# MAX96717_PINOUT.net
KiCad netlist of a schematic drawn in Altium Designer
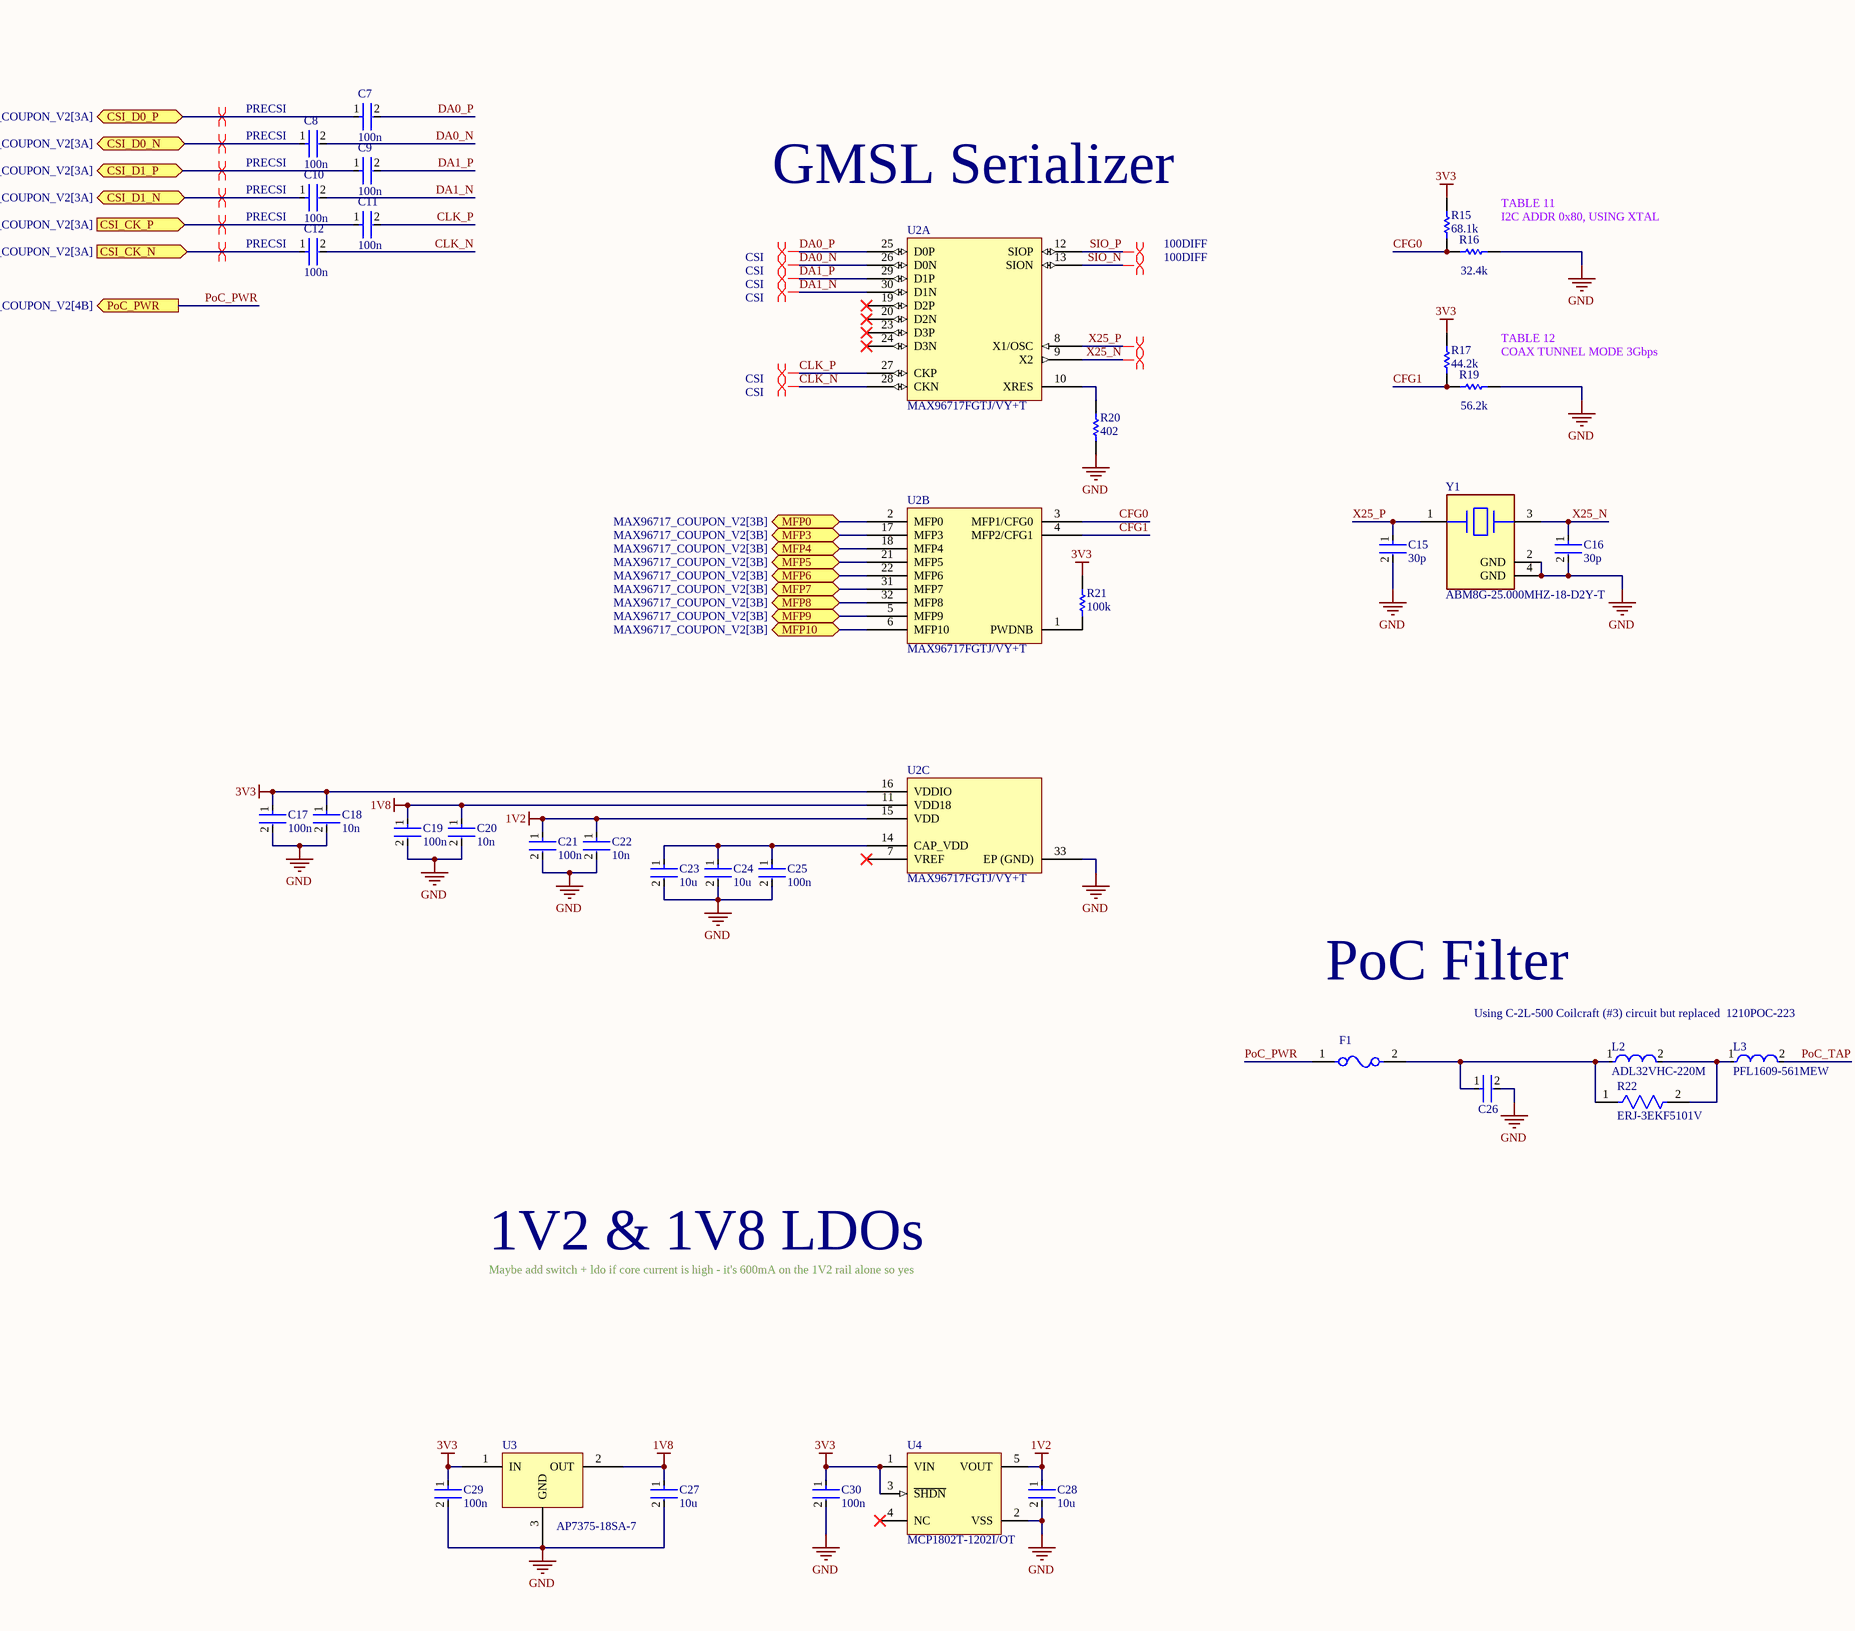
[diagram p0: MAX96717_PINOUT.SchDoc, left]
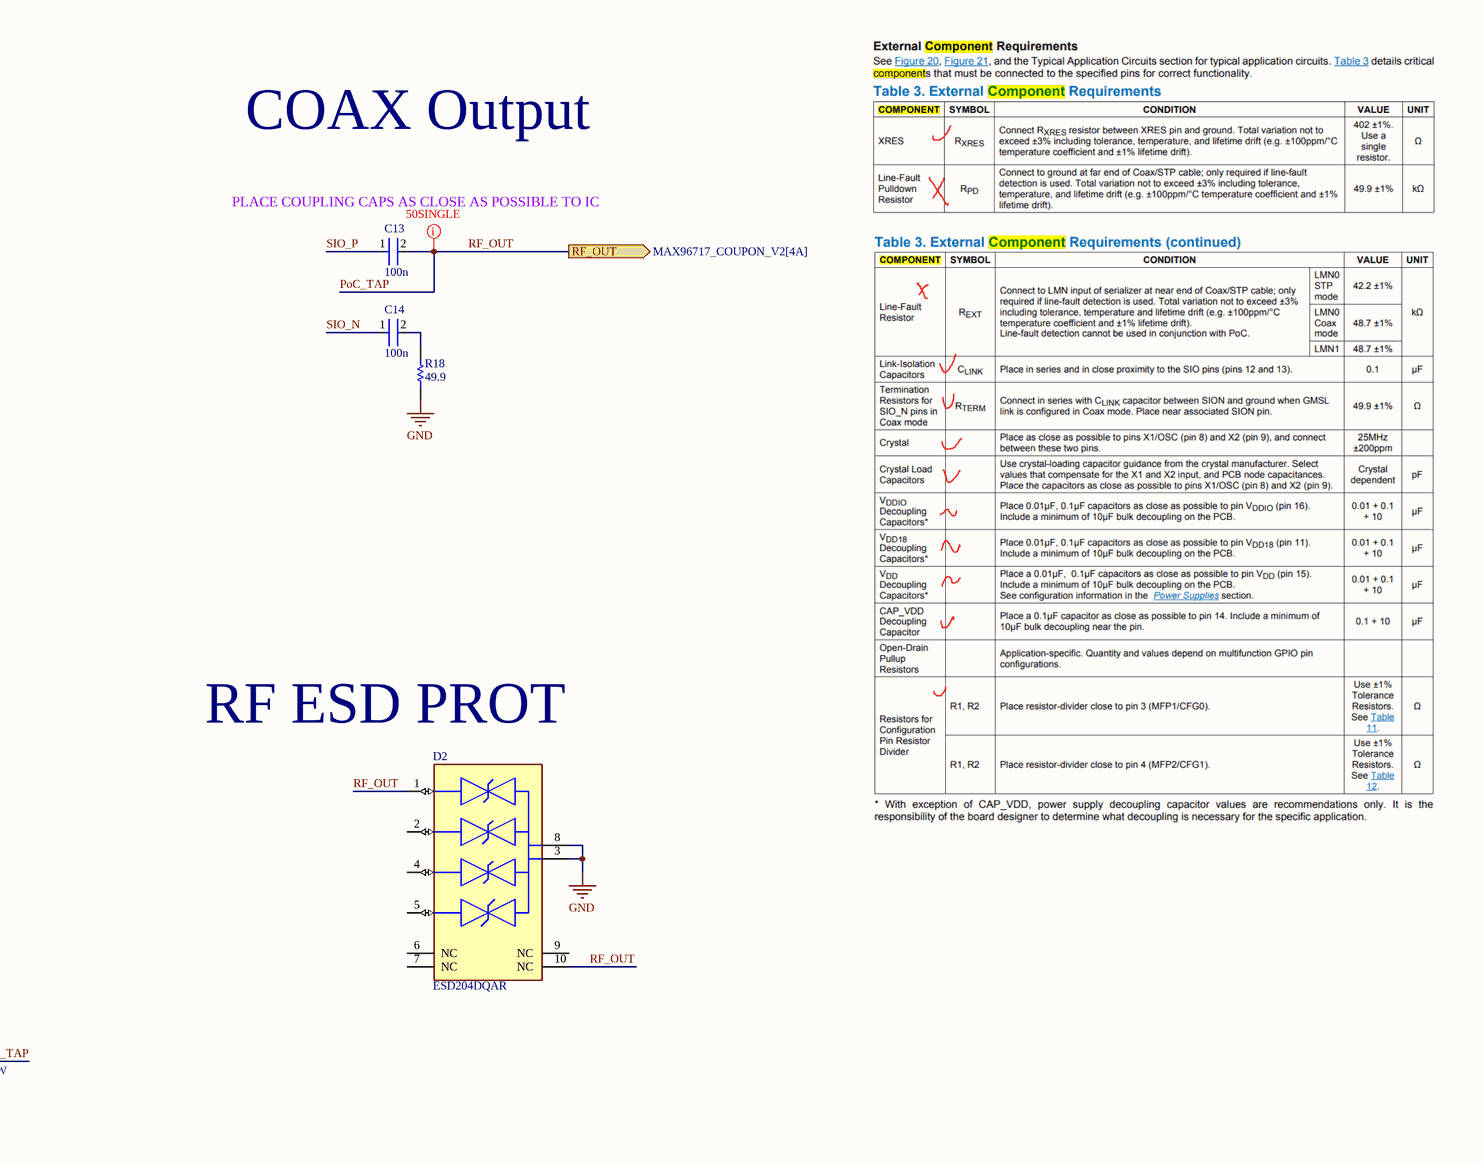
[diagram p1: MAX96717_PINOUT.SchDoc, right]

(export (version "E")
  (design (tool "Eeschema 10.0.6"))
  (components
    (comp (ref "C7")
      (value "100n")
      (footprint "FP-0402-L_1_0_0_05-W_0_5-IPC_A")
      (description "LARGE PADS, 0402 CAP, CHANGE COMMENT TO MATCH REAL P/N")
      (libsource (lib "Space Concordia") (part "b4654b650e69147ec39a6b967a45e02"))
    )
    (comp (ref "C8")
      (value "100n")
      (footprint "FP-0402-L_1_0_0_05-W_0_5-IPC_A")
      (description "LARGE PADS, 0402 CAP, CHANGE COMMENT TO MATCH REAL P/N")
      (libsource (lib "Space Concordia") (part "b4654b650e69147ec39a6b967a45e02"))
    )
    (comp (ref "C9")
      (value "100n")
      (footprint "FP-0402-L_1_0_0_05-W_0_5-IPC_A")
      (description "LARGE PADS, 0402 CAP, CHANGE COMMENT TO MATCH REAL P/N")
      (libsource (lib "Space Concordia") (part "b4654b650e69147ec39a6b967a45e02"))
    )
    (comp (ref "C10")
      (value "100n")
      (footprint "FP-0402-L_1_0_0_05-W_0_5-IPC_A")
      (description "LARGE PADS, 0402 CAP, CHANGE COMMENT TO MATCH REAL P/N")
      (libsource (lib "Space Concordia") (part "b4654b650e69147ec39a6b967a45e02"))
    )
    (comp (ref "C11")
      (value "100n")
      (footprint "FP-0402-L_1_0_0_05-W_0_5-IPC_A")
      (description "LARGE PADS, 0402 CAP, CHANGE COMMENT TO MATCH REAL P/N")
      (libsource (lib "Space Concordia") (part "b4654b650e69147ec39a6b967a45e02"))
    )
    (comp (ref "C12")
      (value "100n")
      (footprint "FP-0402-L_1_0_0_05-W_0_5-IPC_A")
      (description "LARGE PADS, 0402 CAP, CHANGE COMMENT TO MATCH REAL P/N")
      (libsource (lib "Space Concordia") (part "b4654b650e69147ec39a6b967a45e02"))
    )
    (comp (ref "C13")
      (value "100n")
      (footprint "FP-0402-L_1_0_0_05-W_0_5-IPC_A")
      (description "LARGE PADS, 0402 CAP, CHANGE COMMENT TO MATCH REAL P/N")
      (libsource (lib "Space Concordia") (part "b4654b650e69147ec39a6b967a45e02"))
    )
    (comp (ref "C14")
      (value "100n")
      (footprint "FP-0402-L_1_0_0_05-W_0_5-IPC_A")
      (description "LARGE PADS, 0402 CAP, CHANGE COMMENT TO MATCH REAL P/N")
      (libsource (lib "Space Concordia") (part "b4654b650e69147ec39a6b967a45e02"))
    )
    (comp (ref "C15")
      (value "30p")
      (footprint "FP-0402-L_1_0_0_05-W_0_5-IPC_A")
      (description "LARGE PADS, 0402 CAP, CHANGE COMMENT TO MATCH REAL P/N")
      (libsource (lib "Space Concordia") (part "b4654b650e69147ec39a6b967a45e02"))
    )
    (comp (ref "C16")
      (value "30p")
      (footprint "FP-0402-L_1_0_0_05-W_0_5-IPC_A")
      (description "LARGE PADS, 0402 CAP, CHANGE COMMENT TO MATCH REAL P/N")
      (libsource (lib "Space Concordia") (part "b4654b650e69147ec39a6b967a45e02"))
    )
    (comp (ref "C17")
      (value "100n")
      (footprint "FP-0402-L_1_0_0_05-W_0_5-IPC_A")
      (description "LARGE PADS, 0402 CAP, CHANGE COMMENT TO MATCH REAL P/N")
      (libsource (lib "Space Concordia") (part "b4654b650e69147ec39a6b967a45e02"))
    )
    (comp (ref "C18")
      (value "10n")
      (footprint "FP-0402-L_1_0_0_05-W_0_5-IPC_A")
      (description "LARGE PADS, 0402 CAP, CHANGE COMMENT TO MATCH REAL P/N")
      (libsource (lib "Space Concordia") (part "b4654b650e69147ec39a6b967a45e02"))
    )
    (comp (ref "C19")
      (value "100n")
      (footprint "FP-0402-L_1_0_0_05-W_0_5-IPC_A")
      (description "LARGE PADS, 0402 CAP, CHANGE COMMENT TO MATCH REAL P/N")
      (libsource (lib "Space Concordia") (part "b4654b650e69147ec39a6b967a45e02"))
    )
    (comp (ref "C20")
      (value "10n")
      (footprint "FP-0402-L_1_0_0_05-W_0_5-IPC_A")
      (description "LARGE PADS, 0402 CAP, CHANGE COMMENT TO MATCH REAL P/N")
      (libsource (lib "Space Concordia") (part "b4654b650e69147ec39a6b967a45e02"))
    )
    (comp (ref "C21")
      (value "100n")
      (footprint "FP-0402-L_1_0_0_05-W_0_5-IPC_A")
      (description "LARGE PADS, 0402 CAP, CHANGE COMMENT TO MATCH REAL P/N")
      (libsource (lib "Space Concordia") (part "b4654b650e69147ec39a6b967a45e02"))
    )
    (comp (ref "C22")
      (value "10n")
      (footprint "FP-0402-L_1_0_0_05-W_0_5-IPC_A")
      (description "LARGE PADS, 0402 CAP, CHANGE COMMENT TO MATCH REAL P/N")
      (libsource (lib "Space Concordia") (part "b4654b650e69147ec39a6b967a45e02"))
    )
    (comp (ref "C23")
      (value "10u")
      (footprint "FP-0402-L_1_0_0_05-W_0_5-IPC_A")
      (description "LARGE PADS, 0402 CAP, CHANGE COMMENT TO MATCH REAL P/N")
      (libsource (lib "Space Concordia") (part "b4654b650e69147ec39a6b967a45e02"))
    )
    (comp (ref "C24")
      (value "10u")
      (footprint "FP-0402-L_1_0_0_05-W_0_5-IPC_A")
      (description "LARGE PADS, 0402 CAP, CHANGE COMMENT TO MATCH REAL P/N")
      (libsource (lib "Space Concordia") (part "b4654b650e69147ec39a6b967a45e02"))
    )
    (comp (ref "C25")
      (value "100n")
      (footprint "FP-0402-L_1_0_0_05-W_0_5-IPC_A")
      (description "LARGE PADS, 0402 CAP, CHANGE COMMENT TO MATCH REAL P/N")
      (libsource (lib "Space Concordia") (part "b4654b650e69147ec39a6b967a45e02"))
    )
    (comp (ref "C26")
      (value "GRM21BR61E226ME44L")
      (footprint "FP-GRM21B-0_2-e0_2_0_7-IPC_B")
      (description "Chip Multilayer Ceramic Capacitors for General Purpose, 0805, 22uF, X5R, 15%, 20%, 25V")
      (fields (field (name "TOLERANCE") "20%") (field (name "VOLTAGE") "25V"))
      (libsource (lib "Altium Content Vault") (part "b4654b650e69147ec39a6b967a45e02"))
    )
    (comp (ref "C27")
      (value "10u")
      (footprint "FP-0402-L_1_0_0_05-W_0_5-IPC_A")
      (description "LARGE PADS, 0402 CAP, CHANGE COMMENT TO MATCH REAL P/N")
      (libsource (lib "Space Concordia") (part "b4654b650e69147ec39a6b967a45e02"))
    )
    (comp (ref "C28")
      (value "10u")
      (footprint "FP-0402-L_1_0_0_05-W_0_5-IPC_A")
      (description "LARGE PADS, 0402 CAP, CHANGE COMMENT TO MATCH REAL P/N")
      (libsource (lib "Space Concordia") (part "b4654b650e69147ec39a6b967a45e02"))
    )
    (comp (ref "C29")
      (value "100n")
      (footprint "FP-0402-L_1_0_0_05-W_0_5-IPC_A")
      (description "LARGE PADS, 0402 CAP, CHANGE COMMENT TO MATCH REAL P/N")
      (libsource (lib "Space Concordia") (part "b4654b650e69147ec39a6b967a45e02"))
    )
    (comp (ref "C30")
      (value "100n")
      (footprint "FP-0402-L_1_0_0_05-W_0_5-IPC_A")
      (description "LARGE PADS, 0402 CAP, CHANGE COMMENT TO MATCH REAL P/N")
      (libsource (lib "Space Concordia") (part "b4654b650e69147ec39a6b967a45e02"))
    )
    (comp (ref "D2")
      (value "ESD204DQAR")
      (footprint "FP-DQA0010A-MFG")
      (description "4-CHANNEL LOW-CAPACITANCE SURGE")
      (fields
        (field (name "MANUFACTURER") "Texas Instruments")
        (field (name "OCTOPART") "https://octopart.com/esd204dqar-texas+instruments-89917476")
      )
      (libsource (lib "Altium Content Vault") (part "1465e58c1818c7767b55926832f0bf5"))
    )
    (comp (ref "F1")
      (value "MF-FSMF050X-2")
      (footprint "FP-MF-FSMF-MFG")
      (description "PTC RESET FUSE 6V 500MA 0603")
      (fields
        (field (name "MANUFACTURER") "Bourns Inc.")
        (field (name "OCTOPART") "https://octopart.com/mf-fsmf050x-2-bourns-10470804")
      )
      (libsource (lib "Altium Content Vault") (part "5bcf9b9f640e542cf0359d10258e979"))
    )
    (comp (ref "L2")
      (value "ADL32VHC-220M")
      (footprint "FP-1210POC-MFG")
      (description "NOT COILCRAFT - ACTUAL P# --> ADL32VHC-220M\r\n - Power Injection Chokes for PoC")
      (fields
        (field (name "MANUFACTURER") "coilcraft")
        (field (name "OCTOPART") "https://octopart.com/1210poc-223mrc-coilcraft-103207315")
      )
      (libsource (lib "Altium Content Vault") (part "725321dda6339637d4d059423bc1c3c"))
    )
    (comp (ref "L3")
      (value "PFL1609-561MEW")
      (footprint "FP-PFL1609-MFG")
      (description "Fixed Inductors PFL1609 Low Profile 0.56 uH 20 % 1.4 A")
      (fields (field (name "MANUFACTURER") "coilcraft") (field (name "TOLERANCE") "20%"))
      (libsource (lib "Altium Content Vault") (part "725321dda6339637d4d059423bc1c3c"))
    )
    (comp (ref "R15")
      (value "68.1k")
      (footprint "R0603B")
      (description "Resistor")
      (libsource (lib "Space Concordia") (part "Resistor"))
    )
    (comp (ref "R16")
      (value "32.4k")
      (footprint "R0603B")
      (description "Resistor")
      (libsource (lib "Space Concordia") (part "Resistor"))
    )
    (comp (ref "R17")
      (value "44.2k")
      (footprint "R0603B")
      (description "Resistor")
      (libsource (lib "Space Concordia") (part "Resistor"))
    )
    (comp (ref "R18")
      (value "49.9")
      (footprint "R0603B")
      (description "Resistor")
      (libsource (lib "Space Concordia") (part "Resistor"))
    )
    (comp (ref "R19")
      (value "56.2k")
      (footprint "R0603B")
      (description "Resistor")
      (libsource (lib "Space Concordia") (part "Resistor"))
    )
    (comp (ref "R20")
      (value "402")
      (footprint "R0603B")
      (description "Resistor")
      (libsource (lib "Space Concordia") (part "Resistor"))
    )
    (comp (ref "R21")
      (value "100k")
      (footprint "R0603B")
      (description "Resistor")
      (libsource (lib "Space Concordia") (part "Resistor"))
    )
    (comp (ref "R22")
      (value "ERJ-3EKF5101V")
      (footprint "FP-ERJ3EK-MFG")
      (description "RES SMD 5.1K OHM 1% 1/10W 0603")
      (fields (field (name "TOLERANCE") "1%"))
      (libsource (lib "Altium Content Vault") (part "1029c3af85768c4190bb7ad29bc67b5"))
    )
    (comp (ref "U2")
      (value "MAX96717FGTJ/VY+T")
      (footprint "QFN50P500X500X80_HS-33N")
      (description "3Gbps Serializer TQFN-32 Serializers / Deserializers ROHS")
      (libsource (lib "Space Concordia") (part "MAX96717FGTJ_VY+T"))
    )
    (comp (ref "U3")
      (value "AP7375-18SA-7")
      (footprint "AP7375-18SA-7-Footprint-1")
      (description "Fixed Positive LDO Regulator")
      (libsource (lib "Space Concordia") (part "AP7375-18SA-7"))
    )
    (comp (ref "U4")
      (value "MCP1802T-1202I/OT")
      (footprint "SOT-23-OT5_M")
      (description "300 mA, High PSRR, Low Quiescent Current LDO, 5-Pin SOT-23, Industrial Temperature, Tape and Reel")
      (libsource (lib "Altium Content Vault") (part "PM-LINEREG-MCP1802-IL5"))
    )
    (comp (ref "Y1")
      (value "ABM8G-25.000MHZ-18-D2Y-T")
      (footprint "FP-ABM8G-MFG")
      (description "Crystal 25MHz ±20ppm (Tol) ±30ppm (Stability) 18pF FUND 60Ω 4-Pin SMD T/R")
      (fields (field (name "TOLERANCE") "20ppm"))
      (libsource (lib "Altium Content Vault") (part "48e526d86b7f2615d98721063c72f49"))
    )
  )
  (nets
    (net (code "1") (name "/CFG0") (class "Default")
      (node (ref "R15") (pin "1") (pinfunction "1_1") (pintype "passive"))
      (node (ref "R16") (pin "2") (pinfunction "2_2") (pintype "passive"))
      (node (ref "U2") (pin "3") (pinfunction "MFP1/CFG0_3") (pintype "passive"))
    )
    (net (code "2") (name "/CFG1") (class "Default")
      (node (ref "R17") (pin "1") (pinfunction "1_1") (pintype "passive"))
      (node (ref "R19") (pin "2") (pinfunction "2_2") (pintype "passive"))
      (node (ref "U2") (pin "4") (pinfunction "MFP2/CFG1_4") (pintype "passive"))
    )
    (net (code "3") (name "/CLK_N") (class "Default")
      (node (ref "C12") (pin "2") (pinfunction "2_2") (pintype "passive"))
      (node (ref "U2") (pin "28") (pinfunction "CKN_28") (pintype "bidirectional"))
    )
    (net (code "4") (name "/CLK_P") (class "Default")
      (node (ref "C11") (pin "2") (pinfunction "2_2") (pintype "passive"))
      (node (ref "U2") (pin "27") (pinfunction "CKP_27") (pintype "bidirectional"))
    )
    (net (code "5") (name "/CSI_CK_N") (class "Default")
      (node (ref "C12") (pin "1") (pinfunction "1_1") (pintype "passive"))
    )
    (net (code "6") (name "/CSI_CK_P") (class "Default")
      (node (ref "C11") (pin "1") (pinfunction "1_1") (pintype "passive"))
    )
    (net (code "7") (name "/CSI_D0_N") (class "Default")
      (node (ref "C8") (pin "1") (pinfunction "1_1") (pintype "passive"))
    )
    (net (code "8") (name "/CSI_D0_P") (class "Default")
      (node (ref "C7") (pin "1") (pinfunction "1_1") (pintype "passive"))
    )
    (net (code "9") (name "/CSI_D1_N") (class "Default")
      (node (ref "C10") (pin "1") (pinfunction "1_1") (pintype "passive"))
    )
    (net (code "10") (name "/CSI_D1_P") (class "Default")
      (node (ref "C9") (pin "1") (pinfunction "1_1") (pintype "passive"))
    )
    (net (code "11") (name "/DA0_N") (class "Default")
      (node (ref "C8") (pin "2") (pinfunction "2_2") (pintype "passive"))
      (node (ref "U2") (pin "26") (pinfunction "D0N_26") (pintype "bidirectional"))
    )
    (net (code "12") (name "/DA0_P") (class "Default")
      (node (ref "C7") (pin "2") (pinfunction "2_2") (pintype "passive"))
      (node (ref "U2") (pin "25") (pinfunction "D0P_25") (pintype "bidirectional"))
    )
    (net (code "13") (name "/DA1_N") (class "Default")
      (node (ref "C10") (pin "2") (pinfunction "2_2") (pintype "passive"))
      (node (ref "U2") (pin "30") (pinfunction "D1N_30") (pintype "bidirectional"))
    )
    (net (code "14") (name "/DA1_P") (class "Default")
      (node (ref "C9") (pin "2") (pinfunction "2_2") (pintype "passive"))
      (node (ref "U2") (pin "29") (pinfunction "D1P_29") (pintype "bidirectional"))
    )
    (net (code "15") (name "/MFP0") (class "Default")
      (node (ref "U2") (pin "2") (pinfunction "MFP0_2") (pintype "passive"))
    )
    (net (code "16") (name "/MFP3") (class "Default")
      (node (ref "U2") (pin "17") (pinfunction "MFP3_17") (pintype "passive"))
    )
    (net (code "17") (name "/MFP4") (class "Default")
      (node (ref "U2") (pin "18") (pinfunction "MFP4_18") (pintype "passive"))
    )
    (net (code "18") (name "/MFP5") (class "Default")
      (node (ref "U2") (pin "21") (pinfunction "MFP5_21") (pintype "passive"))
    )
    (net (code "19") (name "/MFP6") (class "Default")
      (node (ref "U2") (pin "22") (pinfunction "MFP6_22") (pintype "passive"))
    )
    (net (code "20") (name "/MFP7") (class "Default")
      (node (ref "U2") (pin "31") (pinfunction "MFP7_31") (pintype "passive"))
    )
    (net (code "21") (name "/MFP8") (class "Default")
      (node (ref "U2") (pin "32") (pinfunction "MFP8_32") (pintype "passive"))
    )
    (net (code "22") (name "/MFP9") (class "Default")
      (node (ref "U2") (pin "5") (pinfunction "MFP9_5") (pintype "passive"))
    )
    (net (code "23") (name "/MFP10") (class "Default")
      (node (ref "U2") (pin "6") (pinfunction "MFP10_6") (pintype "passive"))
    )
    (net (code "24") (name "/PoC_PWR") (class "Default")
      (node (ref "F1") (pin "1") (pinfunction "1_1") (pintype "passive"))
    )
    (net (code "25") (name "/PoC_TAP") (class "Default")
      (node (ref "C13") (pin "2") (pinfunction "2_2") (pintype "passive"))
      (node (ref "D2") (pin "1") (pinfunction "IO1_1") (pintype "bidirectional"))
      (node (ref "D2") (pin "10") (pinfunction "NC_10") (pintype "passive"))
      (node (ref "L3") (pin "2") (pinfunction "2_2") (pintype "passive"))
    )
    (net (code "26") (name "/SIO_N") (class "Default")
      (node (ref "C14") (pin "1") (pinfunction "1_1") (pintype "passive"))
      (node (ref "U2") (pin "13") (pinfunction "SION_13") (pintype "bidirectional"))
    )
    (net (code "27") (name "/SIO_P") (class "Default")
      (node (ref "C13") (pin "1") (pinfunction "1_1") (pintype "passive"))
      (node (ref "U2") (pin "12") (pinfunction "SIOP_12") (pintype "bidirectional"))
    )
    (net (code "28") (name "/X25_N") (class "Default")
      (node (ref "C16") (pin "1") (pinfunction "1_1") (pintype "passive"))
      (node (ref "U2") (pin "9") (pinfunction "X2_9") (pintype "output"))
      (node (ref "Y1") (pin "3") (pinfunction "3_3") (pintype "passive"))
    )
    (net (code "29") (name "/X25_P") (class "Default")
      (node (ref "C15") (pin "1") (pinfunction "1_1") (pintype "passive"))
      (node (ref "U2") (pin "8") (pinfunction "X1/OSC_8") (pintype "input"))
      (node (ref "Y1") (pin "1") (pinfunction "1_1") (pintype "passive"))
    )
    (net (code "30") (name "1V2") (class "Default")
      (node (ref "C21") (pin "1") (pinfunction "1_1") (pintype "passive"))
      (node (ref "C22") (pin "1") (pinfunction "1_1") (pintype "passive"))
      (node (ref "C28") (pin "1") (pinfunction "1_1") (pintype "passive"))
      (node (ref "U2") (pin "15") (pinfunction "VDD_15") (pintype "power_in"))
      (node (ref "U4") (pin "5") (pinfunction "VOUT_5") (pintype "power_in"))
    )
    (net (code "31") (name "1V8") (class "Default")
      (node (ref "C19") (pin "1") (pinfunction "1_1") (pintype "passive"))
      (node (ref "C20") (pin "1") (pinfunction "1_1") (pintype "passive"))
      (node (ref "C27") (pin "1") (pinfunction "1_1") (pintype "passive"))
      (node (ref "U2") (pin "11") (pinfunction "VDD18_11") (pintype "power_in"))
      (node (ref "U3") (pin "2") (pinfunction "OUT_2") (pintype "passive"))
    )
    (net (code "32") (name "3V3") (class "Default")
      (node (ref "C17") (pin "1") (pinfunction "1_1") (pintype "passive"))
      (node (ref "C18") (pin "1") (pinfunction "1_1") (pintype "passive"))
      (node (ref "C29") (pin "1") (pinfunction "1_1") (pintype "passive"))
      (node (ref "C30") (pin "1") (pinfunction "1_1") (pintype "passive"))
      (node (ref "R15") (pin "2") (pinfunction "2_2") (pintype "passive"))
      (node (ref "R17") (pin "2") (pinfunction "2_2") (pintype "passive"))
      (node (ref "R21") (pin "2") (pinfunction "2_2") (pintype "passive"))
      (node (ref "U2") (pin "16") (pinfunction "VDDIO_16") (pintype "power_in"))
      (node (ref "U3") (pin "1") (pinfunction "IN_1") (pintype "passive"))
      (node (ref "U4") (pin "1") (pinfunction "VIN_1") (pintype "power_in"))
      (node (ref "U4") (pin "3") (pinfunction "~{SHDN}_3") (pintype "input"))
    )
    (net (code "33") (name "GND") (class "Default")
      (node (ref "C15") (pin "2") (pinfunction "2_2") (pintype "passive"))
      (node (ref "C16") (pin "2") (pinfunction "2_2") (pintype "passive"))
      (node (ref "C17") (pin "2") (pinfunction "2_2") (pintype "passive"))
      (node (ref "C18") (pin "2") (pinfunction "2_2") (pintype "passive"))
      (node (ref "C19") (pin "2") (pinfunction "2_2") (pintype "passive"))
      (node (ref "C20") (pin "2") (pinfunction "2_2") (pintype "passive"))
      (node (ref "C21") (pin "2") (pinfunction "2_2") (pintype "passive"))
      (node (ref "C22") (pin "2") (pinfunction "2_2") (pintype "passive"))
      (node (ref "C23") (pin "2") (pinfunction "2_2") (pintype "passive"))
      (node (ref "C24") (pin "2") (pinfunction "2_2") (pintype "passive"))
      (node (ref "C25") (pin "2") (pinfunction "2_2") (pintype "passive"))
      (node (ref "C26") (pin "2") (pinfunction "2_2") (pintype "passive"))
      (node (ref "C27") (pin "2") (pinfunction "2_2") (pintype "passive"))
      (node (ref "C28") (pin "2") (pinfunction "2_2") (pintype "passive"))
      (node (ref "C29") (pin "2") (pinfunction "2_2") (pintype "passive"))
      (node (ref "C30") (pin "2") (pinfunction "2_2") (pintype "passive"))
      (node (ref "D2") (pin "3") (pinfunction "GND_3") (pintype "power_in"))
      (node (ref "D2") (pin "8") (pinfunction "GND_8") (pintype "power_in"))
      (node (ref "R16") (pin "1") (pinfunction "1_1") (pintype "passive"))
      (node (ref "R18") (pin "1") (pinfunction "1_1") (pintype "passive"))
      (node (ref "R19") (pin "1") (pinfunction "1_1") (pintype "passive"))
      (node (ref "R20") (pin "1") (pinfunction "1_1") (pintype "passive"))
      (node (ref "U2") (pin "33") (pinfunction "EP_(GND)_33") (pintype "power_in"))
      (node (ref "U3") (pin "3") (pinfunction "GND_3") (pintype "passive"))
      (node (ref "U4") (pin "2") (pinfunction "VSS_2") (pintype "power_in"))
      (node (ref "Y1") (pin "2") (pinfunction "GND_2") (pintype "power_in"))
      (node (ref "Y1") (pin "4") (pinfunction "GND_4") (pintype "power_in"))
    )
    (net (code "34") (name "Net-(C14-Pad2)") (class "Default")
      (node (ref "C14") (pin "2") (pinfunction "2_2") (pintype "passive"))
      (node (ref "R18") (pin "2") (pinfunction "2_2") (pintype "passive"))
    )
    (net (code "35") (name "Net-(C26-Pad1)") (class "Default")
      (node (ref "C26") (pin "1") (pinfunction "1_1") (pintype "passive"))
      (node (ref "F1") (pin "2") (pinfunction "2_2") (pintype "passive"))
      (node (ref "L2") (pin "1") (pinfunction "1_1") (pintype "passive"))
      (node (ref "R22") (pin "1") (pinfunction "1_1") (pintype "passive"))
    )
    (net (code "36") (name "Net-(L2-Pad2)") (class "Default")
      (node (ref "L2") (pin "2") (pinfunction "2_2") (pintype "passive"))
      (node (ref "L3") (pin "1") (pinfunction "1_1") (pintype "passive"))
      (node (ref "R22") (pin "2") (pinfunction "2_2") (pintype "passive"))
    )
    (net (code "37") (name "Net-(U2A-XRES)") (class "Default")
      (node (ref "R20") (pin "2") (pinfunction "2_2") (pintype "passive"))
      (node (ref "U2") (pin "10") (pinfunction "XRES_10") (pintype "passive"))
    )
    (net (code "38") (name "Net-(U2B-PWDNB)") (class "Default")
      (node (ref "R21") (pin "1") (pinfunction "1_1") (pintype "passive"))
      (node (ref "U2") (pin "1") (pinfunction "PWDNB_1") (pintype "passive"))
    )
    (net (code "39") (name "Net-(U2C-CAP_VDD)") (class "Default")
      (node (ref "C23") (pin "1") (pinfunction "1_1") (pintype "passive"))
      (node (ref "C24") (pin "1") (pinfunction "1_1") (pintype "passive"))
      (node (ref "C25") (pin "1") (pinfunction "1_1") (pintype "passive"))
      (node (ref "U2") (pin "14") (pinfunction "CAP_VDD_14") (pintype "power_in"))
    )
    (net (code "40") (name "unconnected-(D2-IO2-Pad2)") (class "Default")
      (node (ref "D2") (pin "2") (pinfunction "IO2_2") (pintype "bidirectional"))
    )
    (net (code "41") (name "unconnected-(D2-IO3-Pad4)") (class "Default")
      (node (ref "D2") (pin "4") (pinfunction "IO3_4") (pintype "bidirectional"))
    )
    (net (code "42") (name "unconnected-(D2-IO4-Pad5)") (class "Default")
      (node (ref "D2") (pin "5") (pinfunction "IO4_5") (pintype "bidirectional"))
    )
    (net (code "43") (name "unconnected-(D2-NC-Pad6)") (class "Default")
      (node (ref "D2") (pin "6") (pinfunction "NC_6") (pintype "passive"))
    )
    (net (code "44") (name "unconnected-(D2-NC-Pad7)") (class "Default")
      (node (ref "D2") (pin "7") (pinfunction "NC_7") (pintype "passive"))
    )
    (net (code "45") (name "unconnected-(D2-NC-Pad9)") (class "Default")
      (node (ref "D2") (pin "9") (pinfunction "NC_9") (pintype "passive"))
    )
    (net (code "46") (name "unconnected-(U2A-D2N-Pad20)") (class "Default")
      (node (ref "U2") (pin "20") (pinfunction "D2N_20") (pintype "bidirectional+no_connect"))
    )
    (net (code "47") (name "unconnected-(U2A-D2P-Pad19)") (class "Default")
      (node (ref "U2") (pin "19") (pinfunction "D2P_19") (pintype "bidirectional+no_connect"))
    )
    (net (code "48") (name "unconnected-(U2A-D3N-Pad24)") (class "Default")
      (node (ref "U2") (pin "24") (pinfunction "D3N_24") (pintype "bidirectional+no_connect"))
    )
    (net (code "49") (name "unconnected-(U2A-D3P-Pad23)") (class "Default")
      (node (ref "U2") (pin "23") (pinfunction "D3P_23") (pintype "bidirectional+no_connect"))
    )
    (net (code "50") (name "unconnected-(U2C-VREF-Pad7)") (class "Default")
      (node (ref "U2") (pin "7") (pinfunction "VREF_7") (pintype "power_in+no_connect"))
    )
    (net (code "51") (name "unconnected-(U4-NC-Pad4)") (class "Default")
      (node (ref "U4") (pin "4") (pinfunction "NC_4") (pintype "passive+no_connect"))
    )
  )
)
